# SCHEMATIC.net
KiCad netlist of a schematic drawn in EasyEDA
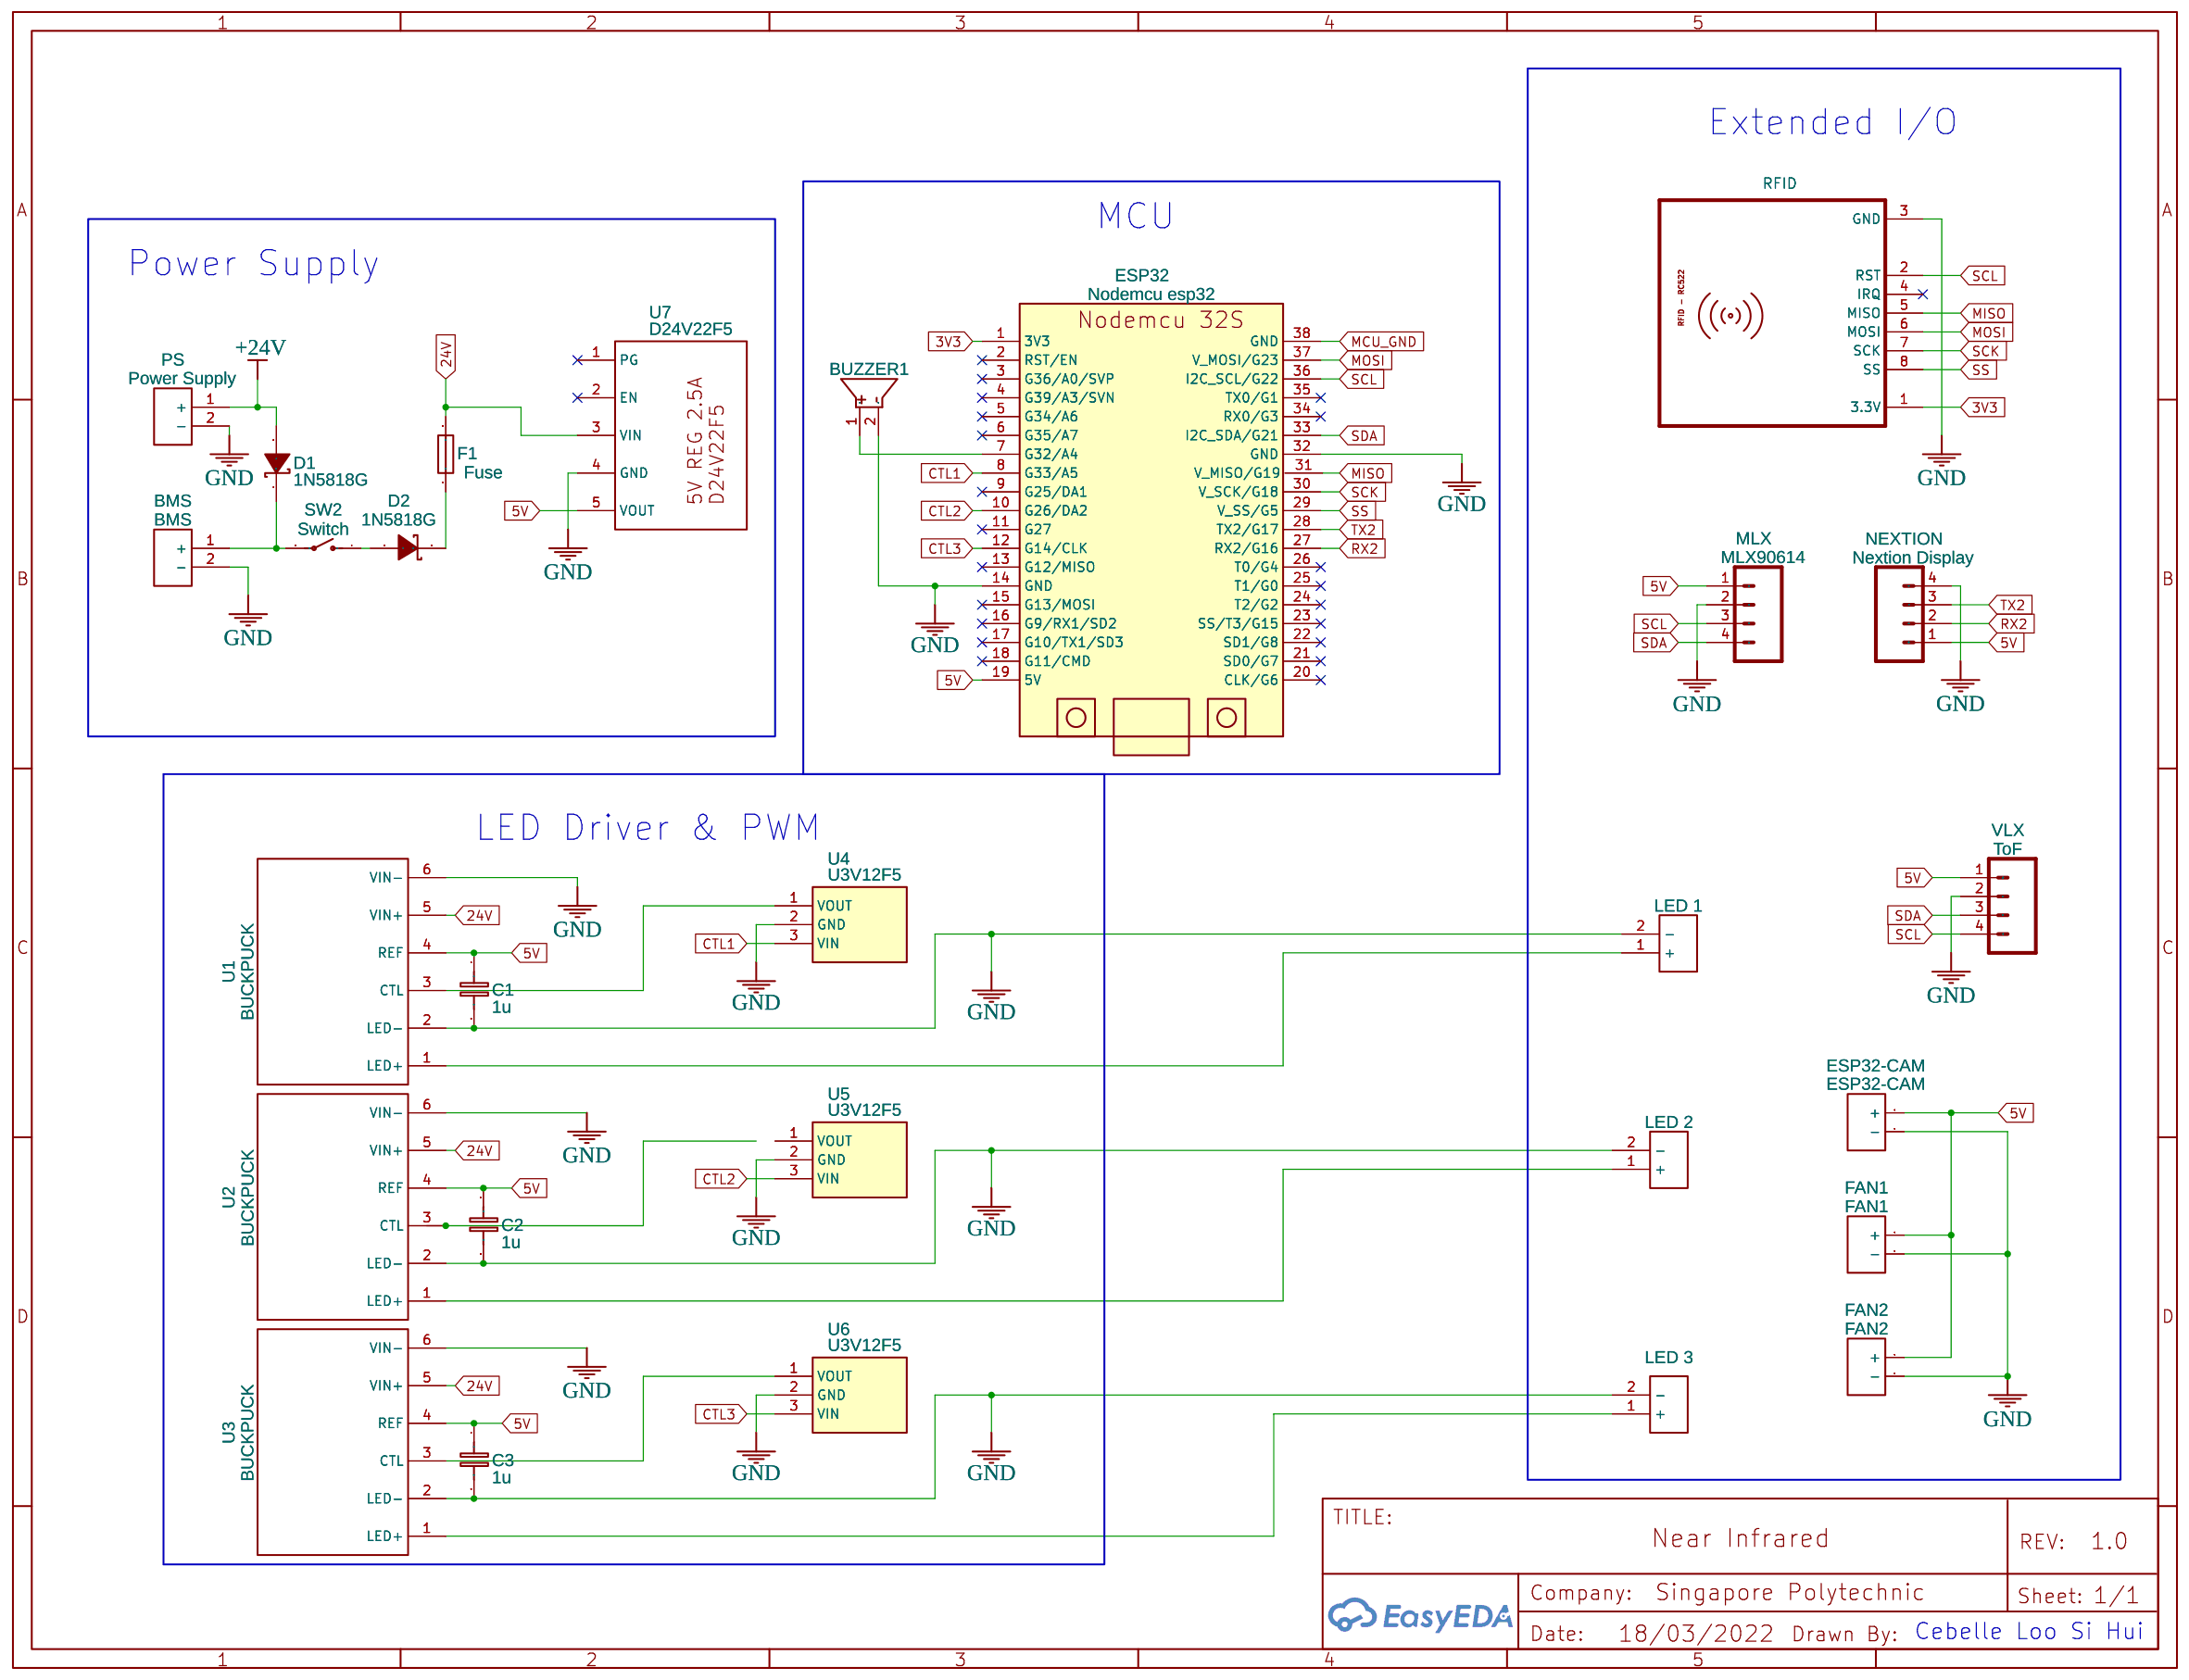
[diagram p0: schematic sheet]

(export (version "E")
  (design (tool "Eeschema 10.0.6"))
  (components
    (comp (ref "BMS")
      (value "BMS")
      (fields
        (field (name "BOM_Manufacturer Part") "WJ103-5.00-2P")
        (field (name "BOM_Supplier Part") "C8439")
      )
      (libsource (lib "") (part "WJ103-5.00-2P_1"))
    )
    (comp (ref "BUZZER1")
      (value "FMQ-BUZZER2")
      (fields (field (name "BOM_Supplier Part") "C9900006103"))
      (libsource (lib "") (part "FMQ-BUZZER2"))
    )
    (comp (ref "C1") (value "1u") (libsource (lib "") (part "CAP-C")))
    (comp (ref "C2") (value "1u") (libsource (lib "") (part "CAP-C")))
    (comp (ref "C3") (value "1u") (libsource (lib "") (part "CAP-C_1")))
    (comp (ref "D1")
      (value "1N5818G")
      (fields (field (name "BOM_Supplier Part") "C232462"))
      (libsource (lib "") (part "1N5818G"))
    )
    (comp (ref "D2")
      (value "1N5818G")
      (fields (field (name "BOM_Supplier Part") "C232462"))
      (libsource (lib "") (part "1N5818G_1"))
    )
    (comp (ref "ESP32") (value "Nodemcu esp32") (libsource (lib "") (part "Nodemcu esp32")))
    (comp (ref "ESP32-CAM")
      (value "ESP32-CAM")
      (fields
        (field (name "BOM_Manufacturer Part") "2.54-1*2PFemale")
        (field (name "BOM_Supplier Part") "C49661")
      )
      (libsource (lib "") (part "Header-Female-2.54_1x2_1"))
    )
    (comp (ref "F1")
      (value "Fuse")
      (fields
        (field (name "BOM_Manufacturer Part") "0251002.NRT1L")
        (field (name "BOM_Supplier Part") "C151088")
      )
      (libsource (lib "") (part "0251002.NRT1L"))
    )
    (comp (ref "FAN1")
      (value "FAN1")
      (fields
        (field (name "BOM_Manufacturer Part") "2.54-1*2PFemale")
        (field (name "BOM_Supplier Part") "C49661")
      )
      (libsource (lib "") (part "Header-Female-2.54_1x2"))
    )
    (comp (ref "FAN2")
      (value "FAN2")
      (fields
        (field (name "BOM_Manufacturer Part") "2.54-1*2PFemale")
        (field (name "BOM_Supplier Part") "C49661")
      )
      (libsource (lib "") (part "Header-Female-2.54_1x2"))
    )
    (comp (ref "LED4")
      (value "LED 1")
      (fields
        (field (name "BOM_Manufacturer Part") "WJ103-5.00-2P")
        (field (name "BOM_Supplier Part") "C8439")
      )
      (libsource (lib "") (part "WJ103-5.00-2P_2"))
    )
    (comp (ref "LED5")
      (value "LED 2")
      (fields
        (field (name "BOM_Manufacturer Part") "WJ103-5.00-2P")
        (field (name "BOM_Supplier Part") "C8439")
      )
      (libsource (lib "") (part "WJ103-5.00-2P_2"))
    )
    (comp (ref "LED6")
      (value "LED 3")
      (fields
        (field (name "BOM_Manufacturer Part") "WJ103-5.00-2P")
        (field (name "BOM_Supplier Part") "C8439")
      )
      (libsource (lib "") (part "WJ103-5.00-2P_2"))
    )
    (comp (ref "MLX") (value "MLX90614") (libsource (lib "") (part "M04POLAR_1")))
    (comp (ref "NEXTION") (value "Nextion Display") (libsource (lib "") (part "M04POLAR_2")))
    (comp (ref "PS")
      (value "Power Supply")
      (fields
        (field (name "BOM_Manufacturer Part") "WJ103-5.00-2P")
        (field (name "BOM_Supplier Part") "C8439")
      )
      (libsource (lib "") (part "WJ103-5.00-2P"))
    )
    (comp (ref "RFID") (value "NO") (libsource (lib "") (part "Unknown_944_-720")))
    (comp (ref "SW2")
      (value "Switch")
      (fields (field (name "BOM_Manufacturer Part") "KCD1-11-1.5x1cm"))
      (libsource (lib "") (part "SWITCH-2P-SPST-Rocker-10x15mm"))
    )
    (comp (ref "U1") (value "BUCKPUCK") (libsource (lib "") (part "BUCKPUCK")))
    (comp (ref "U2") (value "BUCKPUCK") (libsource (lib "") (part "BUCKPUCK")))
    (comp (ref "U3") (value "BUCKPUCK") (libsource (lib "") (part "BUCKPUCK")))
    (comp (ref "U4") (value "U3V12F5") (libsource (lib "") (part "U3V12F5")))
    (comp (ref "U5") (value "U3V12F5") (libsource (lib "") (part "U3V12F5")))
    (comp (ref "U6") (value "U3V12F5") (libsource (lib "") (part "U3V12F5")))
    (comp (ref "U7") (value "D24V22F5") (libsource (lib "") (part "D24V22F5")))
    (comp (ref "VLX") (value "ToF") (libsource (lib "") (part "M04POLAR")))
  )
  (nets
    (net (code "1") (name "+24V") (class "Default")
      (node (ref "D1") (pin "2") (pinfunction "A_2") (pintype "unspecified"))
      (node (ref "PS") (pin "1") (pinfunction "+_1") (pintype "unspecified"))
    )
    (net (code "2") (name "3V3") (class "Default")
      (node (ref "ESP32") (pin "1") (pinfunction "3V3_1") (pintype "passive"))
      (node (ref "RFID") (pin "1") (pinfunction "3.3V_1") (pintype "unspecified"))
    )
    (net (code "3") (name "5V") (class "Default")
      (node (ref "C1") (pin "1") (pinfunction "1_1") (pintype "unspecified"))
      (node (ref "C2") (pin "1") (pinfunction "1_1") (pintype "unspecified"))
      (node (ref "C3") (pin "1") (pinfunction "1_1") (pintype "unspecified"))
      (node (ref "ESP32") (pin "19") (pinfunction "5V_19") (pintype "passive"))
      (node (ref "ESP32-CAM") (pin "2") (pinfunction "+_2") (pintype "input"))
      (node (ref "FAN1") (pin "2") (pinfunction "+_2") (pintype "input"))
      (node (ref "FAN2") (pin "2") (pinfunction "+_2") (pintype "input"))
      (node (ref "MLX") (pin "1") (pinfunction "GND_1") (pintype "unspecified"))
      (node (ref "NEXTION") (pin "1") (pinfunction "GND_1") (pintype "unspecified"))
      (node (ref "U1") (pin "4") (pinfunction "REF_4") (pintype "unspecified"))
      (node (ref "U2") (pin "4") (pinfunction "REF_4") (pintype "unspecified"))
      (node (ref "U3") (pin "4") (pinfunction "REF_4") (pintype "unspecified"))
      (node (ref "U7") (pin "5") (pinfunction "VOUT_5") (pintype "unspecified"))
      (node (ref "VLX") (pin "1") (pinfunction "GND_1") (pintype "unspecified"))
    )
    (net (code "4") (name "24V") (class "Default")
      (node (ref "F1") (pin "2") (pinfunction "2_2") (pintype "unspecified"))
      (node (ref "U1") (pin "5") (pinfunction "VIN+_5") (pintype "unspecified"))
      (node (ref "U2") (pin "5") (pinfunction "VIN+_5") (pintype "unspecified"))
      (node (ref "U3") (pin "5") (pinfunction "VIN+_5") (pintype "unspecified"))
      (node (ref "U7") (pin "3") (pinfunction "VIN_3") (pintype "unspecified"))
    )
    (net (code "5") (name "CTL1") (class "Default")
      (node (ref "ESP32") (pin "8") (pinfunction "G33/A5_8") (pintype "bidirectional"))
      (node (ref "U4") (pin "3") (pinfunction "VIN_3") (pintype "unspecified"))
    )
    (net (code "6") (name "CTL2") (class "Default")
      (node (ref "ESP32") (pin "10") (pinfunction "G26/DA2_10") (pintype "bidirectional"))
      (node (ref "U5") (pin "3") (pinfunction "VIN_3") (pintype "unspecified"))
    )
    (net (code "7") (name "CTL3") (class "Default")
      (node (ref "ESP32") (pin "12") (pinfunction "G14/CLK_12") (pintype "bidirectional"))
      (node (ref "U6") (pin "3") (pinfunction "VIN_3") (pintype "unspecified"))
    )
    (net (code "8") (name "GND") (class "Default")
      (node (ref "BMS") (pin "2") (pinfunction "-_2") (pintype "unspecified"))
      (node (ref "BUZZER1") (pin "2") (pinfunction "2_2") (pintype "unspecified"))
      (node (ref "C1") (pin "2") (pinfunction "2_2") (pintype "unspecified"))
      (node (ref "C2") (pin "2") (pinfunction "2_2") (pintype "unspecified"))
      (node (ref "C3") (pin "2") (pinfunction "2_2") (pintype "unspecified"))
      (node (ref "ESP32") (pin "14") (pinfunction "GND_14") (pintype "passive"))
      (node (ref "ESP32") (pin "32") (pinfunction "GND_32") (pintype "passive"))
      (node (ref "ESP32-CAM") (pin "1") (pinfunction "-_1") (pintype "input"))
      (node (ref "FAN1") (pin "1") (pinfunction "-_1") (pintype "input"))
      (node (ref "FAN2") (pin "1") (pinfunction "-_1") (pintype "input"))
      (node (ref "LED4") (pin "2") (pinfunction "-_2") (pintype "unspecified"))
      (node (ref "LED5") (pin "2") (pinfunction "-_2") (pintype "unspecified"))
      (node (ref "LED6") (pin "2") (pinfunction "-_2") (pintype "unspecified"))
      (node (ref "MLX") (pin "2") (pinfunction "RX_2") (pintype "unspecified"))
      (node (ref "NEXTION") (pin "4") (pinfunction "+5V_4") (pintype "unspecified"))
      (node (ref "PS") (pin "2") (pinfunction "-_2") (pintype "unspecified"))
      (node (ref "RFID") (pin "3") (pinfunction "GND_3") (pintype "unspecified"))
      (node (ref "U1") (pin "2") (pinfunction "LED-_2") (pintype "unspecified"))
      (node (ref "U1") (pin "6") (pinfunction "VIN-_6") (pintype "unspecified"))
      (node (ref "U2") (pin "2") (pinfunction "LED-_2") (pintype "unspecified"))
      (node (ref "U2") (pin "6") (pinfunction "VIN-_6") (pintype "unspecified"))
      (node (ref "U3") (pin "2") (pinfunction "LED-_2") (pintype "unspecified"))
      (node (ref "U3") (pin "6") (pinfunction "VIN-_6") (pintype "unspecified"))
      (node (ref "U4") (pin "2") (pinfunction "GND_2") (pintype "unspecified"))
      (node (ref "U5") (pin "2") (pinfunction "GND_2") (pintype "unspecified"))
      (node (ref "U6") (pin "2") (pinfunction "GND_2") (pintype "unspecified"))
      (node (ref "U7") (pin "4") (pinfunction "GND_4") (pintype "unspecified"))
      (node (ref "VLX") (pin "2") (pinfunction "RX_2") (pintype "unspecified"))
    )
    (net (code "9") (name "MCU_GND") (class "Default")
      (node (ref "ESP32") (pin "38") (pinfunction "GND_38") (pintype "passive"))
    )
    (net (code "10") (name "MISO") (class "Default")
      (node (ref "ESP32") (pin "31") (pinfunction "V_MISO/G19_31") (pintype "bidirectional"))
      (node (ref "RFID") (pin "5") (pinfunction "MISO_5") (pintype "unspecified"))
    )
    (net (code "11") (name "MOSI") (class "Default")
      (node (ref "ESP32") (pin "37") (pinfunction "V_MOSI/G23_37") (pintype "bidirectional"))
      (node (ref "RFID") (pin "6") (pinfunction "MOSI_6") (pintype "unspecified"))
    )
    (net (code "12") (name "Net-(BMS-+)") (class "Default")
      (node (ref "BMS") (pin "1") (pinfunction "+_1") (pintype "unspecified"))
      (node (ref "D1") (pin "1") (pinfunction "C_1") (pintype "unspecified"))
      (node (ref "SW2") (pin "2") (pinfunction "P_2") (pintype "unspecified"))
    )
    (net (code "13") (name "Net-(D2-A)") (class "Default")
      (node (ref "D2") (pin "2") (pinfunction "A_2") (pintype "unspecified"))
      (node (ref "SW2") (pin "1") (pinfunction "O_1") (pintype "unspecified"))
    )
    (net (code "14") (name "Net-(D2-C)") (class "Default")
      (node (ref "D2") (pin "1") (pinfunction "C_1") (pintype "unspecified"))
      (node (ref "F1") (pin "1") (pinfunction "1_1") (pintype "unspecified"))
    )
    (net (code "15") (name "Net-(ESP32-G32{slash}A4)") (class "Default")
      (node (ref "BUZZER1") (pin "1") (pinfunction "1_1") (pintype "unspecified"))
      (node (ref "ESP32") (pin "7") (pinfunction "G32/A4_7") (pintype "bidirectional"))
    )
    (net (code "16") (name "Net-(LED4-+)") (class "Default")
      (node (ref "LED4") (pin "1") (pinfunction "+_1") (pintype "unspecified"))
      (node (ref "U1") (pin "1") (pinfunction "LED+_1") (pintype "unspecified"))
    )
    (net (code "17") (name "Net-(LED5-+)") (class "Default")
      (node (ref "LED5") (pin "1") (pinfunction "+_1") (pintype "unspecified"))
      (node (ref "U2") (pin "1") (pinfunction "LED+_1") (pintype "unspecified"))
    )
    (net (code "18") (name "Net-(LED6-+)") (class "Default")
      (node (ref "LED6") (pin "1") (pinfunction "+_1") (pintype "unspecified"))
      (node (ref "U3") (pin "1") (pinfunction "LED+_1") (pintype "unspecified"))
    )
    (net (code "19") (name "Net-(U1-CTL)") (class "Default")
      (node (ref "U1") (pin "3") (pinfunction "CTL_3") (pintype "unspecified"))
      (node (ref "U4") (pin "1") (pinfunction "VOUT_1") (pintype "unspecified"))
    )
    (net (code "20") (name "Net-(U3-CTL)") (class "Default")
      (node (ref "U3") (pin "3") (pinfunction "CTL_3") (pintype "unspecified"))
      (node (ref "U6") (pin "1") (pinfunction "VOUT_1") (pintype "unspecified"))
    )
    (net (code "21") (name "RX2") (class "Default")
      (node (ref "ESP32") (pin "27") (pinfunction "RX2/G16_27") (pintype "bidirectional"))
      (node (ref "NEXTION") (pin "2") (pinfunction "RX_2") (pintype "unspecified"))
    )
    (net (code "22") (name "SCK") (class "Default")
      (node (ref "ESP32") (pin "30") (pinfunction "V_SCK/G18_30") (pintype "bidirectional"))
      (node (ref "RFID") (pin "7") (pinfunction "SCK_7") (pintype "unspecified"))
    )
    (net (code "23") (name "SCL") (class "Default")
      (node (ref "ESP32") (pin "36") (pinfunction "I2C_SCL/G22_36") (pintype "bidirectional"))
      (node (ref "MLX") (pin "3") (pinfunction "TX_3") (pintype "unspecified"))
      (node (ref "RFID") (pin "2") (pinfunction "RST_2") (pintype "unspecified"))
      (node (ref "VLX") (pin "4") (pinfunction "+5V_4") (pintype "unspecified"))
    )
    (net (code "24") (name "SDA") (class "Default")
      (node (ref "ESP32") (pin "33") (pinfunction "I2C_SDA/G21_33") (pintype "bidirectional"))
      (node (ref "MLX") (pin "4") (pinfunction "+5V_4") (pintype "unspecified"))
      (node (ref "VLX") (pin "3") (pinfunction "TX_3") (pintype "unspecified"))
    )
    (net (code "25") (name "SS") (class "Default")
      (node (ref "ESP32") (pin "29") (pinfunction "V_SS/G5_29") (pintype "bidirectional"))
      (node (ref "RFID") (pin "8") (pinfunction "SS_8") (pintype "unspecified"))
    )
    (net (code "26") (name "TX2") (class "Default")
      (node (ref "ESP32") (pin "28") (pinfunction "TX2/G17_28") (pintype "bidirectional"))
      (node (ref "NEXTION") (pin "3") (pinfunction "TX_3") (pintype "unspecified"))
    )
    (net (code "27") (name "unconnected-(ESP32-CLK{slash}G6-Pad20)") (class "Default")
      (node (ref "ESP32") (pin "20") (pinfunction "CLK/G6_20") (pintype "bidirectional+no_connect"))
    )
    (net (code "28") (name "unconnected-(ESP32-G9{slash}RX1{slash}SD2-Pad16)") (class "Default")
      (node (ref "ESP32") (pin "16") (pinfunction "G9/RX1/SD2_16") (pintype "bidirectional+no_connect"))
    )
    (net (code "29") (name "unconnected-(ESP32-G10{slash}TX1{slash}SD3-Pad17)") (class "Default")
      (node (ref "ESP32") (pin "17") (pinfunction "G10/TX1/SD3_17") (pintype "bidirectional+no_connect"))
    )
    (net (code "30") (name "unconnected-(ESP32-G11{slash}CMD-Pad18)") (class "Default")
      (node (ref "ESP32") (pin "18") (pinfunction "G11/CMD_18") (pintype "bidirectional+no_connect"))
    )
    (net (code "31") (name "unconnected-(ESP32-G12{slash}MISO-Pad13)") (class "Default")
      (node (ref "ESP32") (pin "13") (pinfunction "G12/MISO_13") (pintype "bidirectional+no_connect"))
    )
    (net (code "32") (name "unconnected-(ESP32-G13{slash}MOSI-Pad15)") (class "Default")
      (node (ref "ESP32") (pin "15") (pinfunction "G13/MOSI_15") (pintype "bidirectional+no_connect"))
    )
    (net (code "33") (name "unconnected-(ESP32-G25{slash}DA1-Pad9)") (class "Default")
      (node (ref "ESP32") (pin "9") (pinfunction "G25/DA1_9") (pintype "bidirectional+no_connect"))
    )
    (net (code "34") (name "unconnected-(ESP32-G27-Pad11)") (class "Default")
      (node (ref "ESP32") (pin "11") (pinfunction "G27_11") (pintype "bidirectional+no_connect"))
    )
    (net (code "35") (name "unconnected-(ESP32-G34{slash}A6-Pad5)") (class "Default")
      (node (ref "ESP32") (pin "5") (pinfunction "G34/A6_5") (pintype "bidirectional+no_connect"))
    )
    (net (code "36") (name "unconnected-(ESP32-G35{slash}A7-Pad6)") (class "Default")
      (node (ref "ESP32") (pin "6") (pinfunction "G35/A7_6") (pintype "bidirectional+no_connect"))
    )
    (net (code "37") (name "unconnected-(ESP32-G36{slash}A0{slash}SVP-Pad3)") (class "Default")
      (node (ref "ESP32") (pin "3") (pinfunction "G36/A0/SVP_3") (pintype "bidirectional+no_connect"))
    )
    (net (code "38") (name "unconnected-(ESP32-G39{slash}A3{slash}SVN-Pad4)") (class "Default")
      (node (ref "ESP32") (pin "4") (pinfunction "G39/A3/SVN_4") (pintype "bidirectional+no_connect"))
    )
    (net (code "39") (name "unconnected-(ESP32-RST{slash}EN-Pad2)") (class "Default")
      (node (ref "ESP32") (pin "2") (pinfunction "RST/EN_2") (pintype "bidirectional+no_connect"))
    )
    (net (code "40") (name "unconnected-(ESP32-RX0{slash}G3-Pad34)") (class "Default")
      (node (ref "ESP32") (pin "34") (pinfunction "RX0/G3_34") (pintype "bidirectional+no_connect"))
    )
    (net (code "41") (name "unconnected-(ESP32-SD0{slash}G7-Pad21)") (class "Default")
      (node (ref "ESP32") (pin "21") (pinfunction "SD0/G7_21") (pintype "bidirectional+no_connect"))
    )
    (net (code "42") (name "unconnected-(ESP32-SD1{slash}G8-Pad22)") (class "Default")
      (node (ref "ESP32") (pin "22") (pinfunction "SD1/G8_22") (pintype "bidirectional+no_connect"))
    )
    (net (code "43") (name "unconnected-(ESP32-SS{slash}T3{slash}G15-Pad23)") (class "Default")
      (node (ref "ESP32") (pin "23") (pinfunction "SS/T3/G15_23") (pintype "bidirectional+no_connect"))
    )
    (net (code "44") (name "unconnected-(ESP32-T0{slash}G4-Pad26)") (class "Default")
      (node (ref "ESP32") (pin "26") (pinfunction "T0/G4_26") (pintype "bidirectional+no_connect"))
    )
    (net (code "45") (name "unconnected-(ESP32-T1{slash}G0-Pad25)") (class "Default")
      (node (ref "ESP32") (pin "25") (pinfunction "T1/G0_25") (pintype "bidirectional+no_connect"))
    )
    (net (code "46") (name "unconnected-(ESP32-T2{slash}G2-Pad24)") (class "Default")
      (node (ref "ESP32") (pin "24") (pinfunction "T2/G2_24") (pintype "bidirectional+no_connect"))
    )
    (net (code "47") (name "unconnected-(ESP32-TX0{slash}G1-Pad35)") (class "Default")
      (node (ref "ESP32") (pin "35") (pinfunction "TX0/G1_35") (pintype "bidirectional+no_connect"))
    )
    (net (code "48") (name "unconnected-(RFID-IRQ-Pad4)") (class "Default")
      (node (ref "RFID") (pin "4") (pinfunction "IRQ_4") (pintype "unspecified+no_connect"))
    )
    (net (code "49") (name "unconnected-(U2-CTL-Pad3)") (class "Default")
      (node (ref "U2") (pin "3") (pinfunction "CTL_3") (pintype "unspecified"))
    )
    (net (code "50") (name "unconnected-(U5-VOUT-Pad1)") (class "Default")
      (node (ref "U5") (pin "1") (pinfunction "VOUT_1") (pintype "unspecified"))
    )
    (net (code "51") (name "unconnected-(U7-EN-Pad2)") (class "Default")
      (node (ref "U7") (pin "2") (pinfunction "EN_2") (pintype "unspecified+no_connect"))
    )
    (net (code "52") (name "unconnected-(U7-PG-Pad1)") (class "Default")
      (node (ref "U7") (pin "1") (pinfunction "PG_1") (pintype "unspecified+no_connect"))
    )
  )
)
